# First_Project.net
KiCad netlist of a schematic drawn in Altium Designer
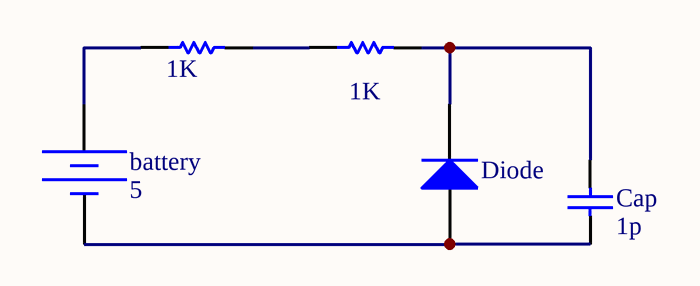
[diagram p0: First Project.SchDoc]

(export (version "E")
  (design (tool "Eeschema 10.0.6"))
  (components
    (comp (ref "battery")
      (value "Constant Voltage Source")
      (fields (field (name "DC MAGNITUDE") "5"))
      (libsource (lib "Simulation Generic Components") (part "Battery"))
    )
    (comp (ref "Cap")
      (value "1p")
      (description "Capacitor")
      (libsource (lib "Simulation Generic Components") (part "Capacitor"))
    )
    (comp (ref "Diode") (value "Diode") (libsource (lib "Simulation Generic Components") (part "Diode")))
    (comp (ref "R1")
      (value "1K")
      (description "Resistor")
      (libsource (lib "Simulation Generic Components") (part "Resistor"))
    )
    (comp (ref "R2")
      (value "1K")
      (description "Resistor")
      (libsource (lib "Simulation Generic Components") (part "Resistor"))
    )
  )
  (nets
    (net (code "1") (name "Net-(Diode-A)") (class "Default")
      (node (ref "Cap") (pin "1") (pinfunction "1_1") (pintype "passive"))
      (node (ref "Diode") (pin "1") (pinfunction "A_1") (pintype "passive"))
      (node (ref "battery") (pin "2") (pinfunction "2_2") (pintype "passive"))
    )
    (net (code "2") (name "Net-(Diode-K)") (class "Default")
      (node (ref "Cap") (pin "2") (pinfunction "2_2") (pintype "passive"))
      (node (ref "Diode") (pin "2") (pinfunction "K_2") (pintype "passive"))
      (node (ref "R2") (pin "2") (pinfunction "2_2") (pintype "passive"))
    )
    (net (code "3") (name "Net-(R1-Pad1)") (class "Default")
      (node (ref "R1") (pin "1") (pinfunction "1_1") (pintype "passive"))
      (node (ref "battery") (pin "1") (pinfunction "1_1") (pintype "passive"))
    )
    (net (code "4") (name "Net-(R1-Pad2)") (class "Default")
      (node (ref "R1") (pin "2") (pinfunction "2_2") (pintype "passive"))
      (node (ref "R2") (pin "1") (pinfunction "1_1") (pintype "passive"))
    )
  )
)
